# piezo-preamp-tickler_V3-dual-supply-TL07.net
KiCad netlist of a schematic drawn in EAGLE
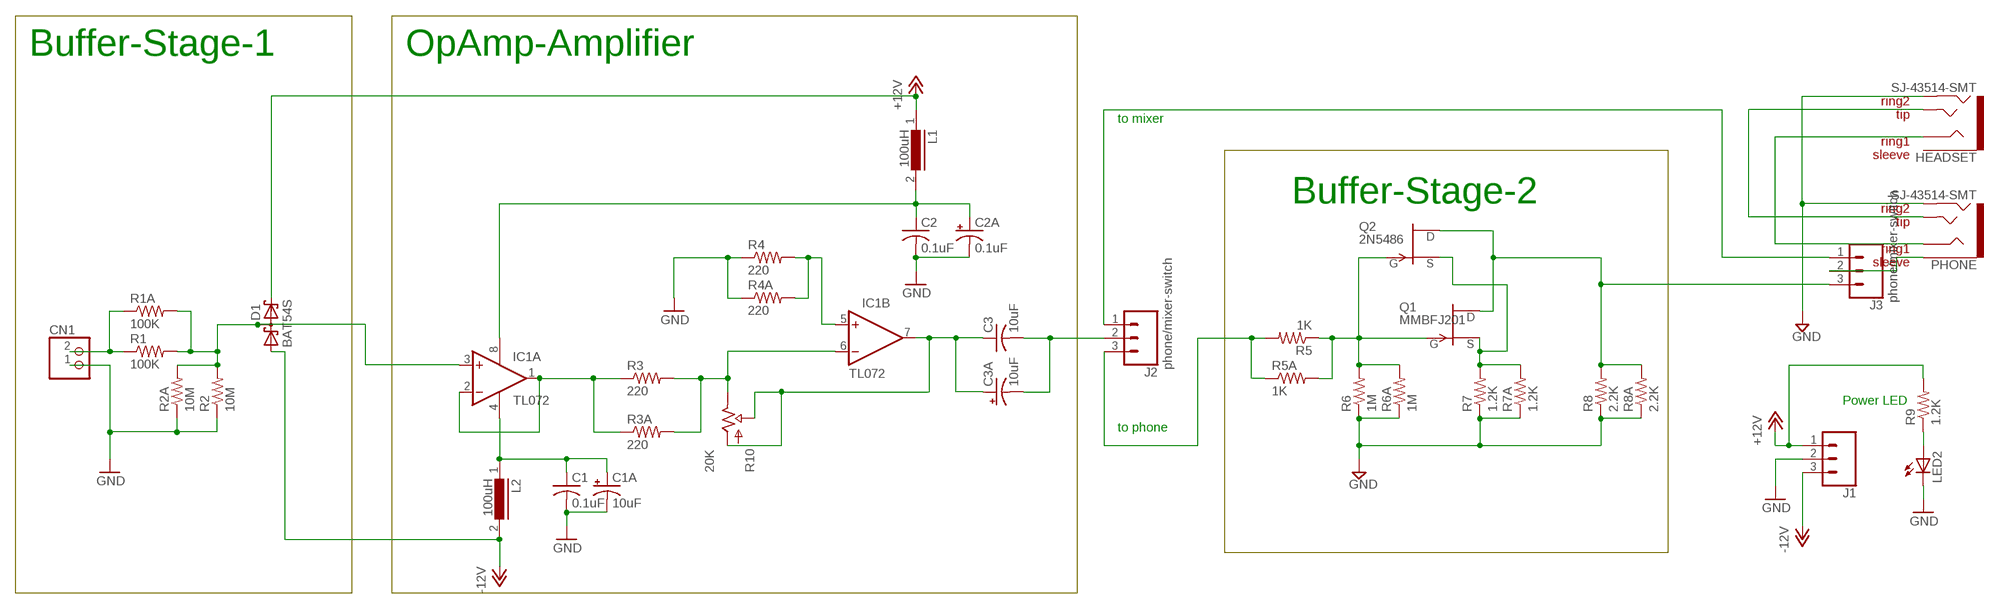
[diagram p0: schematic, sheet 1]

(export (version "E")
  (design (tool "Eeschema 10.0.6"))
  (components
    (comp (ref "C1")
      (value "0.1uF")
      (footprint "eagle-import:C0805K")
      (libsource (lib "eagle-import") (part "C-USC0805K"))
    )
    (comp (ref "C1A")
      (value "10uF")
      (footprint "eagle-import:E2,5-6E")
      (libsource (lib "eagle-import") (part "CPOL-USE2,5-6E"))
    )
    (comp (ref "C2")
      (value "0.1uF")
      (footprint "eagle-import:C0805K")
      (libsource (lib "eagle-import") (part "C-USC0805K"))
    )
    (comp (ref "C2A")
      (value "0.1uF")
      (footprint "eagle-import:E2,5-6E")
      (libsource (lib "eagle-import") (part "CPOL-USE2,5-6E"))
    )
    (comp (ref "C3")
      (value "10uF")
      (footprint "eagle-import:C1206")
      (libsource (lib "eagle-import") (part "C-USC1206"))
    )
    (comp (ref "C3A")
      (value "10uF")
      (footprint "eagle-import:E2,5-6E")
      (libsource (lib "eagle-import") (part "CPOL-USE2,5-6E"))
    )
    (comp (ref "CN1")
      (value "JST_2PIN-THM")
      (footprint "eagle-import:JST-PH-2-THM")
      (libsource (lib "eagle-import") (part "JST_2PIN-THM"))
    )
    (comp (ref "D1")
      (value "BAT54S")
      (footprint "eagle-import:SOT23")
      (libsource (lib "eagle-import") (part "BAT54S"))
    )
    (comp (ref "HEADSET")
      (value "SJ-43514-SMT")
      (footprint "eagle-import:TRRS_SJ-43514-SMT-TR")
      (libsource (lib "eagle-import") (part "TRRS-3.5MMLGPADS"))
    )
    (comp (ref "IC1")
      (value "TL072")
      (footprint "eagle-import:SO08")
      (libsource (lib "eagle-import") (part "OPA2UA134"))
    )
    (comp (ref "J1")
      (value "CONN_03LOCK")
      (footprint "eagle-import:1X03_LOCK")
      (libsource (lib "eagle-import") (part "CONN_03LOCK"))
    )
    (comp (ref "J2")
      (value "phone/mixer-switch")
      (footprint "eagle-import:1X03_LOCK")
      (libsource (lib "eagle-import") (part "CONN_03LOCK"))
    )
    (comp (ref "J3")
      (value "phone/mixer-switch")
      (footprint "eagle-import:1X03_LOCK")
      (libsource (lib "eagle-import") (part "CONN_03LOCK"))
    )
    (comp (ref "L1")
      (value "100uH")
      (footprint "eagle-import:LBC-SE")
      (libsource (lib "eagle-import") (part "LBC-SE"))
    )
    (comp (ref "L2")
      (value "100uH")
      (footprint "eagle-import:LBC-SE")
      (libsource (lib "eagle-import") (part "LBC-SE"))
    )
    (comp (ref "LED2")
      (value "LED3MM")
      (footprint "eagle-import:LED3MM")
      (libsource (lib "eagle-import") (part "LED3MM"))
    )
    (comp (ref "PHONE")
      (value "SJ-43514-SMT")
      (footprint "eagle-import:TRRS_SJ-43514-SMT-TR")
      (libsource (lib "eagle-import") (part "TRRS-3.5MMLGPADS"))
    )
    (comp (ref "Q1")
      (value "MMBFJ201")
      (footprint "eagle-import:SOT23")
      (libsource (lib "eagle-import") (part "transistor-fet_396_?548SST4"))
    )
    (comp (ref "Q2")
      (value "2N5486")
      (footprint "eagle-import:TO92-")
      (libsource (lib "eagle-import") (part "?5482N6"))
    )
    (comp (ref "R1")
      (value "100K")
      (footprint "eagle-import:R0603")
      (libsource (lib "eagle-import") (part "R-US_R0603"))
    )
    (comp (ref "R1A")
      (value "100K")
      (footprint "eagle-import:0204V")
      (libsource (lib "eagle-import") (part "R-US_0204/2V"))
    )
    (comp (ref "R2")
      (value "10M")
      (footprint "eagle-import:R0603")
      (libsource (lib "eagle-import") (part "R-US_R0603"))
    )
    (comp (ref "R2A")
      (value "10M")
      (footprint "eagle-import:0204V")
      (libsource (lib "eagle-import") (part "R-US_0204/2V"))
    )
    (comp (ref "R3")
      (value "220")
      (footprint "eagle-import:R0603")
      (libsource (lib "eagle-import") (part "R-US_R0603"))
    )
    (comp (ref "R3A")
      (value "220")
      (footprint "eagle-import:0204V")
      (libsource (lib "eagle-import") (part "R-US_0204/2V"))
    )
    (comp (ref "R4")
      (value "220")
      (footprint "eagle-import:R0603")
      (libsource (lib "eagle-import") (part "R-US_R0603"))
    )
    (comp (ref "R4A")
      (value "220")
      (footprint "eagle-import:0204V")
      (libsource (lib "eagle-import") (part "R-US_0204/2V"))
    )
    (comp (ref "R5")
      (value "1K")
      (footprint "eagle-import:R0603")
      (libsource (lib "eagle-import") (part "R-US_R0603"))
    )
    (comp (ref "R5A")
      (value "1K")
      (footprint "eagle-import:0204V")
      (libsource (lib "eagle-import") (part "R-US_0204/2V"))
    )
    (comp (ref "R6")
      (value "1M")
      (footprint "eagle-import:R0603")
      (libsource (lib "eagle-import") (part "R-US_R0603"))
    )
    (comp (ref "R6A")
      (value "1M")
      (footprint "eagle-import:0204V")
      (libsource (lib "eagle-import") (part "R-US_0204/2V"))
    )
    (comp (ref "R7")
      (value "1.2K")
      (footprint "eagle-import:R0603")
      (libsource (lib "eagle-import") (part "R-US_R0603"))
    )
    (comp (ref "R7A")
      (value "1.2K")
      (footprint "eagle-import:0204V")
      (libsource (lib "eagle-import") (part "R-US_0204/2V"))
    )
    (comp (ref "R8")
      (value "2.2K")
      (footprint "eagle-import:R0603")
      (libsource (lib "eagle-import") (part "R-US_R0603"))
    )
    (comp (ref "R8A")
      (value "2.2K")
      (footprint "eagle-import:0204V")
      (libsource (lib "eagle-import") (part "R-US_0204/2V"))
    )
    (comp (ref "R9")
      (value "1.2K")
      (footprint "eagle-import:0204V")
      (libsource (lib "eagle-import") (part "R-US_0204/2V"))
    )
    (comp (ref "R10")
      (value "20K")
      (footprint "eagle-import:TRIMPOT-MULTI")
      (libsource (lib "eagle-import") (part "POTTRIMPOT-MULTI"))
    )
  )
  (nets
    (net (code "1") (name "+12V") (class "Default")
      (node (ref "D1") (pin "2") (pinfunction "C2_2") (pintype "passive"))
      (node (ref "J1") (pin "1") (pinfunction "1_1") (pintype "passive"))
      (node (ref "L1") (pin "1") (pinfunction "1_1") (pintype "passive"))
      (node (ref "R9") (pin "2") (pinfunction "2_2") (pintype "passive"))
    )
    (net (code "2") (name "-12V") (class "Default")
      (node (ref "D1") (pin "1") (pinfunction "A1_1") (pintype "passive"))
      (node (ref "J1") (pin "3") (pinfunction "3_3") (pintype "passive"))
      (node (ref "L2") (pin "2") (pinfunction "2_2") (pintype "passive"))
    )
    (net (code "3") (name "GND") (class "Default")
      (node (ref "C1") (pin "2") (pinfunction "2_2") (pintype "passive"))
      (node (ref "C1A") (pin "-") (pinfunction "-_-") (pintype "passive"))
      (node (ref "C2") (pin "2") (pinfunction "2_2") (pintype "passive"))
      (node (ref "C2A") (pin "-") (pinfunction "-_-") (pintype "passive"))
      (node (ref "CN1") (pin "1") (pinfunction "2_1") (pintype "passive"))
      (node (ref "HEADSET") (pin "RING2") (pinfunction "RING2_RING2") (pintype "bidirectional"))
      (node (ref "J1") (pin "2") (pinfunction "2_2") (pintype "passive"))
      (node (ref "LED2") (pin "K") (pinfunction "C_K") (pintype "passive"))
      (node (ref "PHONE") (pin "RING2") (pinfunction "RING2_RING2") (pintype "bidirectional"))
      (node (ref "R2") (pin "1") (pinfunction "1_1") (pintype "passive"))
      (node (ref "R2A") (pin "1") (pinfunction "1_1") (pintype "passive"))
      (node (ref "R4") (pin "1") (pinfunction "1_1") (pintype "passive"))
      (node (ref "R4A") (pin "1") (pinfunction "1_1") (pintype "passive"))
      (node (ref "R6") (pin "1") (pinfunction "1_1") (pintype "passive"))
      (node (ref "R6A") (pin "1") (pinfunction "1_1") (pintype "passive"))
      (node (ref "R7") (pin "1") (pinfunction "1_1") (pintype "passive"))
      (node (ref "R7A") (pin "1") (pinfunction "1_1") (pintype "passive"))
      (node (ref "R8") (pin "1") (pinfunction "1_1") (pintype "passive"))
      (node (ref "R8A") (pin "1") (pinfunction "1_1") (pintype "passive"))
    )
    (net (code "4") (name "Net-(C3-Pad2)") (class "Default")
      (node (ref "C3") (pin "2") (pinfunction "2_2") (pintype "passive"))
      (node (ref "C3A") (pin "-") (pinfunction "-_-") (pintype "passive"))
      (node (ref "J2") (pin "2") (pinfunction "2_2") (pintype "passive"))
    )
    (net (code "5") (name "Net-(CN1-1)") (class "Default")
      (node (ref "CN1") (pin "2") (pinfunction "1_2") (pintype "passive"))
      (node (ref "R1") (pin "1") (pinfunction "1_1") (pintype "passive"))
      (node (ref "R1A") (pin "1") (pinfunction "1_1") (pintype "passive"))
    )
    (net (code "6") (name "Net-(D1-C1A2)") (class "Default")
      (node (ref "D1") (pin "3") (pinfunction "C1A2_3") (pintype "passive"))
      (node (ref "IC1") (pin "3") (pinfunction "+IN_3") (pintype "input"))
      (node (ref "R1") (pin "2") (pinfunction "2_2") (pintype "passive"))
      (node (ref "R1A") (pin "2") (pinfunction "2_2") (pintype "passive"))
      (node (ref "R2") (pin "2") (pinfunction "2_2") (pintype "passive"))
      (node (ref "R2A") (pin "2") (pinfunction "2_2") (pintype "passive"))
    )
    (net (code "7") (name "Net-(HEADSET-PadRING1)") (class "Default")
      (node (ref "HEADSET") (pin "RING1") (pinfunction "RING1_RING1") (pintype "bidirectional"))
      (node (ref "PHONE") (pin "RING1") (pinfunction "RING1_RING1") (pintype "bidirectional"))
    )
    (net (code "8") (name "Net-(HEADSET-PadTIP)") (class "Default")
      (node (ref "HEADSET") (pin "TIP") (pinfunction "TIP_TIP") (pintype "bidirectional"))
      (node (ref "PHONE") (pin "TIP") (pinfunction "TIP_TIP") (pintype "bidirectional"))
    )
    (net (code "9") (name "Net-(IC1A--IN)") (class "Default")
      (node (ref "IC1") (pin "1") (pinfunction "OUT_1") (pintype "output"))
      (node (ref "IC1") (pin "2") (pinfunction "-IN_2") (pintype "input"))
      (node (ref "R3") (pin "1") (pinfunction "1_1") (pintype "passive"))
      (node (ref "R3A") (pin "1") (pinfunction "1_1") (pintype "passive"))
    )
    (net (code "10") (name "Net-(IC1A-V+)") (class "Default")
      (node (ref "C2") (pin "1") (pinfunction "1_1") (pintype "passive"))
      (node (ref "C2A") (pin "+") (pinfunction "+_+") (pintype "passive"))
      (node (ref "IC1") (pin "8") (pinfunction "V+_8") (pintype "power_in"))
      (node (ref "L1") (pin "2") (pinfunction "2_2") (pintype "passive"))
    )
    (net (code "11") (name "Net-(IC1A-V-)") (class "Default")
      (node (ref "C1") (pin "1") (pinfunction "1_1") (pintype "passive"))
      (node (ref "C1A") (pin "+") (pinfunction "+_+") (pintype "passive"))
      (node (ref "IC1") (pin "4") (pinfunction "V-_4") (pintype "power_in"))
      (node (ref "L2") (pin "1") (pinfunction "1_1") (pintype "passive"))
    )
    (net (code "12") (name "Net-(IC1B-+IN)") (class "Default")
      (node (ref "IC1") (pin "5") (pinfunction "+IN_5") (pintype "input"))
      (node (ref "R4") (pin "2") (pinfunction "2_2") (pintype "passive"))
      (node (ref "R4A") (pin "2") (pinfunction "2_2") (pintype "passive"))
    )
    (net (code "13") (name "Net-(IC1B--IN)") (class "Default")
      (node (ref "IC1") (pin "6") (pinfunction "-IN_6") (pintype "input"))
      (node (ref "R10") (pin "P$1") (pinfunction "OUT_P$1") (pintype "passive"))
      (node (ref "R10") (pin "P$3") (pinfunction "OUT_P$3") (pintype "passive"))
      (node (ref "R10") (pin "P$4") (pinfunction "OUT_P$4") (pintype "passive"))
      (node (ref "R10") (pin "P$6") (pinfunction "OUT_P$6") (pintype "passive"))
      (node (ref "R10") (pin "P$9") (pinfunction "OUT_P$9") (pintype "passive"))
      (node (ref "R3") (pin "2") (pinfunction "2_2") (pintype "passive"))
      (node (ref "R3A") (pin "2") (pinfunction "2_2") (pintype "passive"))
    )
    (net (code "14") (name "Net-(IC1B-OUT)") (class "Default")
      (node (ref "C3") (pin "1") (pinfunction "1_1") (pintype "passive"))
      (node (ref "C3A") (pin "+") (pinfunction "+_+") (pintype "passive"))
      (node (ref "IC1") (pin "7") (pinfunction "OUT_7") (pintype "output"))
      (node (ref "R10") (pin "P$10") (pinfunction "WIPER_P$10") (pintype "passive"))
      (node (ref "R10") (pin "P$12") (pinfunction "WIPER_P$12") (pintype "passive"))
      (node (ref "R10") (pin "P$13") (pinfunction "WIPER_P$13") (pintype "passive"))
      (node (ref "R10") (pin "P$15") (pinfunction "WIPER_P$15") (pintype "passive"))
      (node (ref "R10") (pin "P$16") (pinfunction "WIPER_P$16") (pintype "passive"))
      (node (ref "R10") (pin "P$18") (pinfunction "WIPER_P$18") (pintype "passive"))
      (node (ref "R10") (pin "P$20") (pinfunction "IN_P$20") (pintype "passive"))
      (node (ref "R10") (pin "P$21") (pinfunction "IN_P$21") (pintype "passive"))
      (node (ref "R10") (pin "P$22") (pinfunction "IN_P$22") (pintype "passive"))
      (node (ref "R10") (pin "P$24") (pinfunction "IN_P$24") (pintype "passive"))
      (node (ref "R10") (pin "P$27") (pinfunction "IN_P$27") (pintype "passive"))
    )
    (net (code "15") (name "Net-(J2-Pad1)") (class "Default")
      (node (ref "J2") (pin "1") (pinfunction "1_1") (pintype "passive"))
      (node (ref "J3") (pin "1") (pinfunction "1_1") (pintype "passive"))
    )
    (net (code "16") (name "Net-(J2-Pad3)") (class "Default")
      (node (ref "J2") (pin "3") (pinfunction "3_3") (pintype "passive"))
      (node (ref "R5") (pin "2") (pinfunction "2_2") (pintype "passive"))
      (node (ref "R5A") (pin "1") (pinfunction "1_1") (pintype "passive"))
    )
    (net (code "17") (name "Net-(J3-Pad2)") (class "Default")
      (node (ref "J3") (pin "2") (pinfunction "2_2") (pintype "passive"))
      (node (ref "PHONE") (pin "EARTH") (pinfunction "EARTH_EARTH") (pintype "bidirectional"))
    )
    (net (code "18") (name "Net-(LED2-PadA)") (class "Default")
      (node (ref "LED2") (pin "A") (pinfunction "A_A") (pintype "passive"))
      (node (ref "R9") (pin "1") (pinfunction "1_1") (pintype "passive"))
    )
    (net (code "19") (name "Net-(Q1-D)") (class "Default")
      (node (ref "J3") (pin "3") (pinfunction "3_3") (pintype "passive"))
      (node (ref "Q1") (pin "1") (pinfunction "D_1") (pintype "passive"))
      (node (ref "Q2") (pin "3") (pinfunction "D_3") (pintype "passive"))
      (node (ref "R8") (pin "2") (pinfunction "2_2") (pintype "passive"))
      (node (ref "R8A") (pin "2") (pinfunction "2_2") (pintype "passive"))
    )
    (net (code "20") (name "Net-(Q1-G)") (class "Default")
      (node (ref "Q1") (pin "3") (pinfunction "G_3") (pintype "passive"))
      (node (ref "Q2") (pin "1") (pinfunction "G_1") (pintype "passive"))
      (node (ref "R5") (pin "1") (pinfunction "1_1") (pintype "passive"))
      (node (ref "R5A") (pin "2") (pinfunction "2_2") (pintype "passive"))
      (node (ref "R6") (pin "2") (pinfunction "2_2") (pintype "passive"))
      (node (ref "R6A") (pin "2") (pinfunction "2_2") (pintype "passive"))
    )
    (net (code "21") (name "Net-(Q1-S)") (class "Default")
      (node (ref "Q1") (pin "2") (pinfunction "S_2") (pintype "passive"))
      (node (ref "Q2") (pin "2") (pinfunction "S_2") (pintype "passive"))
      (node (ref "R7") (pin "2") (pinfunction "2_2") (pintype "passive"))
      (node (ref "R7A") (pin "2") (pinfunction "2_2") (pintype "passive"))
    )
    (net (code "22") (name "unconnected-(HEADSET-PadEARTH)") (class "Default")
      (node (ref "HEADSET") (pin "EARTH") (pinfunction "EARTH_EARTH") (pintype "bidirectional"))
    )
  )
)
